# big7segment.net
KiCad netlist of a schematic drawn in EAGLE
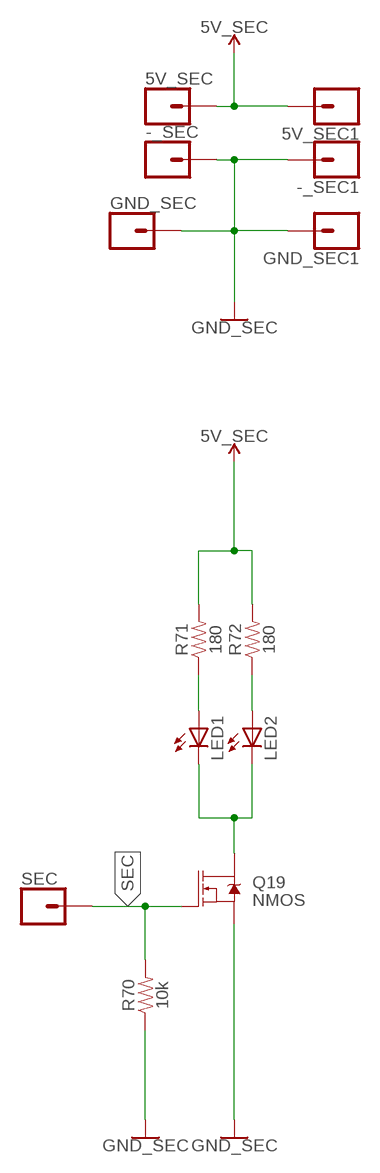
[diagram p0: schematic, sheet 1]

(export (version "E")
  (design (tool "Eeschema 10.0.6"))
  (components
    (comp (ref "-_SEC")
      (value "CONN_01OFFSET")
      (footprint "eagle-import:1X01_OFFSET")
      (libsource (lib "eagle-import") (part "CONN_01OFFSET"))
    )
    (comp (ref "-_SEC1")
      (value "CONN_01OFFSET")
      (footprint "eagle-import:1X01_OFFSET")
      (libsource (lib "eagle-import") (part "CONN_01OFFSET"))
    )
    (comp (ref "5V_SEC")
      (value "CONN_01OFFSET")
      (footprint "eagle-import:1X01_OFFSET")
      (libsource (lib "eagle-import") (part "CONN_01OFFSET"))
    )
    (comp (ref "5V_SEC1")
      (value "CONN_01OFFSET")
      (footprint "eagle-import:1X01_OFFSET")
      (libsource (lib "eagle-import") (part "CONN_01OFFSET"))
    )
    (comp (ref "GND_SEC")
      (value "CONN_01OFFSET")
      (footprint "eagle-import:1X01_OFFSET")
      (libsource (lib "eagle-import") (part "CONN_01OFFSET"))
    )
    (comp (ref "GND_SEC1")
      (value "CONN_01OFFSET")
      (footprint "eagle-import:1X01_OFFSET")
      (libsource (lib "eagle-import") (part "CONN_01OFFSET"))
    )
    (comp (ref "LED1")
      (value "LED5MM")
      (footprint "eagle-import:LED5MM")
      (libsource (lib "eagle-import") (part "LED5MM"))
    )
    (comp (ref "LED2")
      (value "LED5MM")
      (footprint "eagle-import:LED5MM")
      (libsource (lib "eagle-import") (part "LED5MM"))
    )
    (comp (ref "Q19")
      (value "NMOS")
      (footprint "eagle-import:SOT23-3")
      (libsource (lib "eagle-import") (part "MOSFET-NCH-AO3404A"))
    )
    (comp (ref "R70")
      (value "10k")
      (footprint "eagle-import:0805")
      (libsource (lib "eagle-import") (part "0.3OHM-0805-1/8W-1%"))
    )
    (comp (ref "R71")
      (value "180")
      (footprint "eagle-import:0805")
      (libsource (lib "eagle-import") (part "0.3OHM-0805-1/8W-1%"))
    )
    (comp (ref "R72")
      (value "180")
      (footprint "eagle-import:0805")
      (libsource (lib "eagle-import") (part "0.3OHM-0805-1/8W-1%"))
    )
    (comp (ref "SEC")
      (value "CONN_01OFFSET")
      (footprint "eagle-import:1X01_OFFSET")
      (libsource (lib "eagle-import") (part "CONN_01OFFSET"))
    )
  )
  (nets
    (net (code "1") (name "5V_SEC") (class "Default")
      (node (ref "5V_SEC") (pin "1") (pinfunction "1_1") (pintype "passive"))
      (node (ref "5V_SEC1") (pin "1") (pinfunction "1_1") (pintype "passive"))
      (node (ref "R71") (pin "2") (pinfunction "2_2") (pintype "passive"))
      (node (ref "R72") (pin "2") (pinfunction "2_2") (pintype "passive"))
    )
    (net (code "2") (name "GND_SEC") (class "Default")
      (node (ref "-_SEC") (pin "1") (pinfunction "1_1") (pintype "passive"))
      (node (ref "-_SEC1") (pin "1") (pinfunction "1_1") (pintype "passive"))
      (node (ref "GND_SEC") (pin "1") (pinfunction "1_1") (pintype "passive"))
      (node (ref "GND_SEC1") (pin "1") (pinfunction "1_1") (pintype "passive"))
      (node (ref "Q19") (pin "2") (pinfunction "S_2") (pintype "bidirectional"))
      (node (ref "R70") (pin "1") (pinfunction "1_1") (pintype "passive"))
    )
    (net (code "3") (name "Net-(LED1-C)") (class "Default")
      (node (ref "LED1") (pin "K") (pinfunction "C_K") (pintype "passive"))
      (node (ref "LED2") (pin "K") (pinfunction "C_K") (pintype "passive"))
      (node (ref "Q19") (pin "3") (pinfunction "D_3") (pintype "bidirectional"))
    )
    (net (code "4") (name "Net-(LED1-PadA)") (class "Default")
      (node (ref "LED1") (pin "A") (pinfunction "A_A") (pintype "passive"))
      (node (ref "R71") (pin "1") (pinfunction "1_1") (pintype "passive"))
    )
    (net (code "5") (name "Net-(LED2-PadA)") (class "Default")
      (node (ref "LED2") (pin "A") (pinfunction "A_A") (pintype "passive"))
      (node (ref "R72") (pin "1") (pinfunction "1_1") (pintype "passive"))
    )
    (net (code "6") (name "SEC") (class "Default")
      (node (ref "Q19") (pin "1") (pinfunction "G_1") (pintype "bidirectional"))
      (node (ref "R70") (pin "2") (pinfunction "2_2") (pintype "passive"))
      (node (ref "SEC") (pin "1") (pinfunction "1_1") (pintype "passive"))
    )
  )
)
